# L000-Power-Schematic.net
KiCad netlist of a schematic drawn in EAGLE
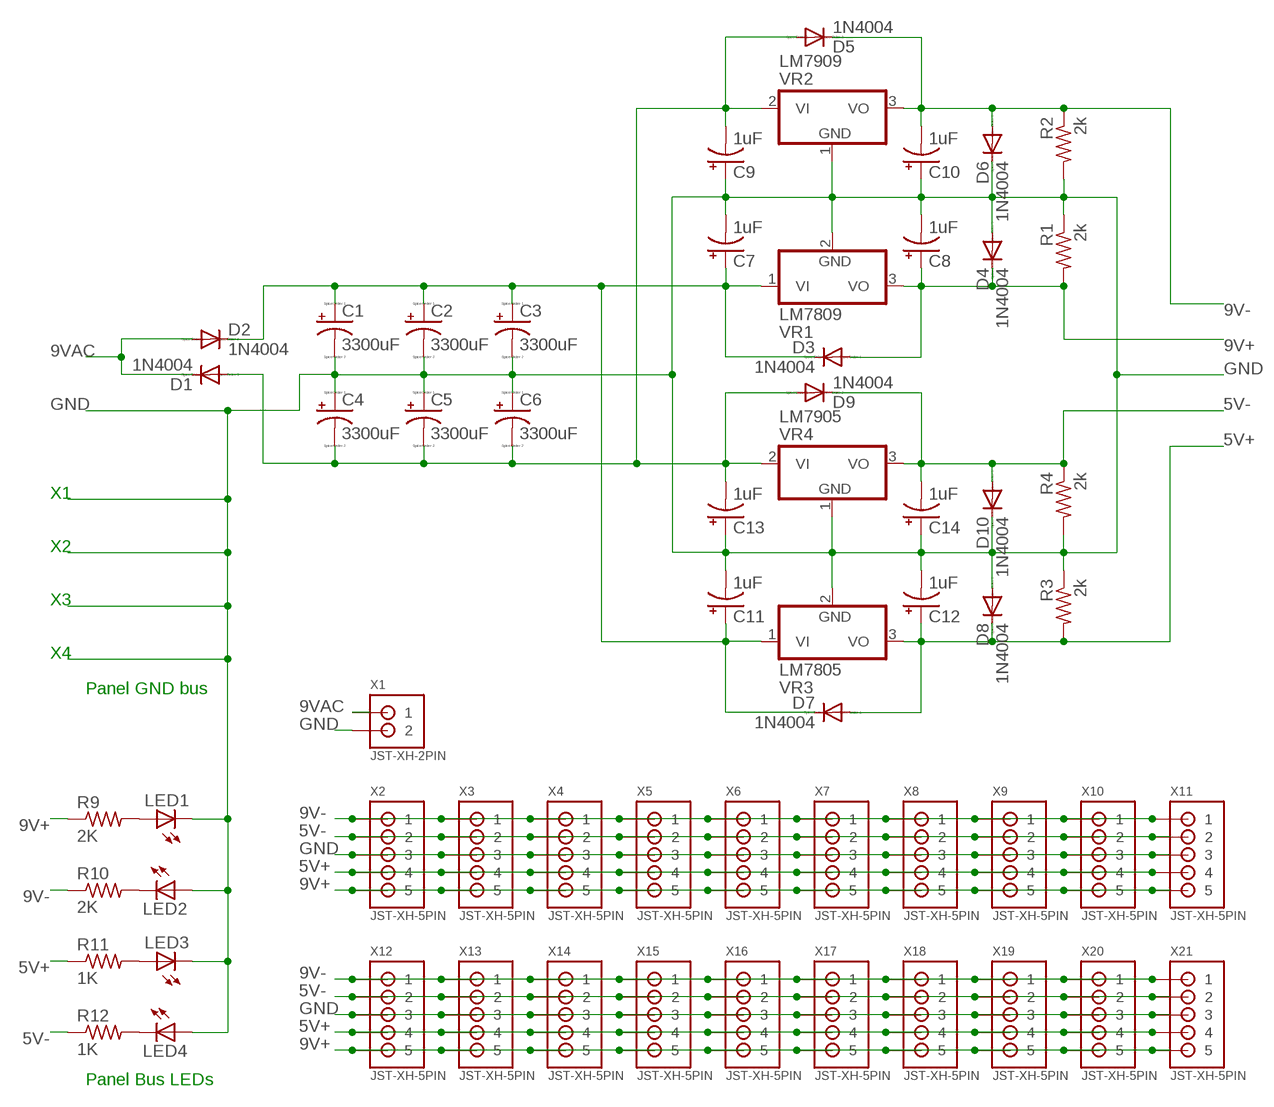
[diagram p0: schematic, sheet 1]

(export (version "E")
  (design (tool "Eeschema 10.0.6"))
  (components
    (comp (ref "C1")
      (value "3300uF")
      (footprint "eagle-import:E5-13")
      (libsource (lib "eagle-import") (part "resistor_CPOL-USE5-13"))
    )
    (comp (ref "C2")
      (value "3300uF")
      (footprint "eagle-import:E5-13")
      (libsource (lib "eagle-import") (part "resistor_CPOL-USE5-13"))
    )
    (comp (ref "C3")
      (value "3300uF")
      (footprint "eagle-import:E5-13")
      (libsource (lib "eagle-import") (part "resistor_CPOL-USE5-13"))
    )
    (comp (ref "C4")
      (value "3300uF")
      (footprint "eagle-import:E5-13")
      (libsource (lib "eagle-import") (part "resistor_CPOL-USE5-13"))
    )
    (comp (ref "C5")
      (value "3300uF")
      (footprint "eagle-import:E5-13")
      (libsource (lib "eagle-import") (part "resistor_CPOL-USE5-13"))
    )
    (comp (ref "C6")
      (value "3300uF")
      (footprint "eagle-import:E5-13")
      (libsource (lib "eagle-import") (part "resistor_CPOL-USE5-13"))
    )
    (comp (ref "C7")
      (value "1uF")
      (footprint "eagle-import:E2,5-6E")
      (libsource (lib "eagle-import") (part "CPOL-USE2,5-6E"))
    )
    (comp (ref "C8")
      (value "1uF")
      (footprint "eagle-import:E2,5-6E")
      (libsource (lib "eagle-import") (part "CPOL-USE2,5-6E"))
    )
    (comp (ref "C9")
      (value "1uF")
      (footprint "eagle-import:E2,5-6E")
      (libsource (lib "eagle-import") (part "CPOL-USE2,5-6E"))
    )
    (comp (ref "C10")
      (value "1uF")
      (footprint "eagle-import:E2,5-6E")
      (libsource (lib "eagle-import") (part "CPOL-USE2,5-6E"))
    )
    (comp (ref "C11")
      (value "1uF")
      (footprint "eagle-import:E2,5-6E")
      (libsource (lib "eagle-import") (part "CPOL-USE2,5-6E"))
    )
    (comp (ref "C12")
      (value "1uF")
      (footprint "eagle-import:E2,5-6E")
      (libsource (lib "eagle-import") (part "CPOL-USE2,5-6E"))
    )
    (comp (ref "C13")
      (value "1uF")
      (footprint "eagle-import:E2,5-6E")
      (libsource (lib "eagle-import") (part "CPOL-USE2,5-6E"))
    )
    (comp (ref "C14")
      (value "1uF")
      (footprint "eagle-import:E2,5-6E")
      (libsource (lib "eagle-import") (part "CPOL-USE2,5-6E"))
    )
    (comp (ref "D1")
      (value "1N4004")
      (footprint "eagle-import:DO41-10")
      (libsource (lib "eagle-import") (part "1N4004"))
    )
    (comp (ref "D2")
      (value "1N4004")
      (footprint "eagle-import:DO41-10")
      (libsource (lib "eagle-import") (part "1N4004"))
    )
    (comp (ref "D3")
      (value "1N4004")
      (footprint "eagle-import:DO41-10")
      (libsource (lib "eagle-import") (part "1N4004"))
    )
    (comp (ref "D4")
      (value "1N4004")
      (footprint "eagle-import:DO41-10")
      (libsource (lib "eagle-import") (part "1N4004"))
    )
    (comp (ref "D5")
      (value "1N4004")
      (footprint "eagle-import:DO41-10")
      (libsource (lib "eagle-import") (part "1N4004"))
    )
    (comp (ref "D6")
      (value "1N4004")
      (footprint "eagle-import:DO41-10")
      (libsource (lib "eagle-import") (part "1N4004"))
    )
    (comp (ref "D7")
      (value "1N4004")
      (footprint "eagle-import:DO41-10")
      (libsource (lib "eagle-import") (part "1N4004"))
    )
    (comp (ref "D8")
      (value "1N4004")
      (footprint "eagle-import:DO41-10")
      (libsource (lib "eagle-import") (part "1N4004"))
    )
    (comp (ref "D9")
      (value "1N4004")
      (footprint "eagle-import:DO41-10")
      (libsource (lib "eagle-import") (part "1N4004"))
    )
    (comp (ref "D10")
      (value "1N4004")
      (footprint "eagle-import:DO41-10")
      (libsource (lib "eagle-import") (part "1N4004"))
    )
    (comp (ref "LED1")
      (value "LED5MM")
      (footprint "eagle-import:LED5MM")
      (libsource (lib "eagle-import") (part "LED5MM"))
    )
    (comp (ref "LED2")
      (value "LED5MM")
      (footprint "eagle-import:LED5MM")
      (libsource (lib "eagle-import") (part "LED5MM"))
    )
    (comp (ref "LED3")
      (value "LED5MM")
      (footprint "eagle-import:LED5MM")
      (libsource (lib "eagle-import") (part "LED5MM"))
    )
    (comp (ref "LED4")
      (value "LED5MM")
      (footprint "eagle-import:LED5MM")
      (libsource (lib "eagle-import") (part "LED5MM"))
    )
    (comp (ref "R1")
      (value "2k")
      (footprint "eagle-import:0309_10")
      (libsource (lib "eagle-import") (part "R-US_0309/10"))
    )
    (comp (ref "R2")
      (value "2k")
      (footprint "eagle-import:0309_10")
      (libsource (lib "eagle-import") (part "R-US_0309/10"))
    )
    (comp (ref "R3")
      (value "2k")
      (footprint "eagle-import:0309_10")
      (libsource (lib "eagle-import") (part "R-US_0309/10"))
    )
    (comp (ref "R4")
      (value "2k")
      (footprint "eagle-import:0309_10")
      (libsource (lib "eagle-import") (part "R-US_0309/10"))
    )
    (comp (ref "R9")
      (value "2K")
      (footprint "eagle-import:0309_10")
      (libsource (lib "eagle-import") (part "R-US_0309/10"))
    )
    (comp (ref "R10")
      (value "2K")
      (footprint "eagle-import:0309_10")
      (libsource (lib "eagle-import") (part "R-US_0309/10"))
    )
    (comp (ref "R11")
      (value "1K")
      (footprint "eagle-import:0309_10")
      (libsource (lib "eagle-import") (part "R-US_0309/10"))
    )
    (comp (ref "R12")
      (value "1K")
      (footprint "eagle-import:0309_10")
      (libsource (lib "eagle-import") (part "R-US_0309/10"))
    )
    (comp (ref "VR1")
      (value "LM7809")
      (footprint "eagle-import:TO220H")
      (libsource (lib "eagle-import") (part "78T08"))
    )
    (comp (ref "VR2")
      (value "LM7909")
      (footprint "eagle-import:TO220H")
      (libsource (lib "eagle-import") (part "79T08"))
    )
    (comp (ref "VR3")
      (value "LM7805")
      (footprint "eagle-import:TO220H")
      (libsource (lib "eagle-import") (part "78T05"))
    )
    (comp (ref "VR4")
      (value "LM7905")
      (footprint "eagle-import:TO220H")
      (libsource (lib "eagle-import") (part "79T05"))
    )
    (comp (ref "X1")
      (value "JST-XH-2PIN")
      (footprint "eagle-import:JST_B2B-PH_HEADER")
      (libsource (lib "eagle-import") (part "JST-PH_2-PIN_HEADER"))
    )
    (comp (ref "X2")
      (value "JST-XH-5PIN")
      (footprint "eagle-import:JST_B5B-PH_HEADER")
      (libsource (lib "eagle-import") (part "JST-PH_5-PIN_HEADER"))
    )
    (comp (ref "X3")
      (value "JST-XH-5PIN")
      (footprint "eagle-import:JST_B5B-PH_HEADER")
      (libsource (lib "eagle-import") (part "JST-PH_5-PIN_HEADER"))
    )
    (comp (ref "X4")
      (value "JST-XH-5PIN")
      (footprint "eagle-import:JST_B5B-PH_HEADER")
      (libsource (lib "eagle-import") (part "JST-PH_5-PIN_HEADER"))
    )
    (comp (ref "X5")
      (value "JST-XH-5PIN")
      (footprint "eagle-import:JST_B5B-PH_HEADER")
      (libsource (lib "eagle-import") (part "JST-PH_5-PIN_HEADER"))
    )
    (comp (ref "X6")
      (value "JST-XH-5PIN")
      (footprint "eagle-import:JST_B5B-PH_HEADER")
      (libsource (lib "eagle-import") (part "JST-PH_5-PIN_HEADER"))
    )
    (comp (ref "X7")
      (value "JST-XH-5PIN")
      (footprint "eagle-import:JST_B5B-PH_HEADER")
      (libsource (lib "eagle-import") (part "JST-PH_5-PIN_HEADER"))
    )
    (comp (ref "X8")
      (value "JST-XH-5PIN")
      (footprint "eagle-import:JST_B5B-PH_HEADER")
      (libsource (lib "eagle-import") (part "JST-PH_5-PIN_HEADER"))
    )
    (comp (ref "X9")
      (value "JST-XH-5PIN")
      (footprint "eagle-import:JST_B5B-PH_HEADER")
      (libsource (lib "eagle-import") (part "JST-PH_5-PIN_HEADER"))
    )
    (comp (ref "X10")
      (value "JST-XH-5PIN")
      (footprint "eagle-import:JST_B5B-PH_HEADER")
      (libsource (lib "eagle-import") (part "JST-PH_5-PIN_HEADER"))
    )
    (comp (ref "X11")
      (value "JST-XH-5PIN")
      (footprint "eagle-import:JST_B5B-PH_HEADER")
      (libsource (lib "eagle-import") (part "JST-PH_5-PIN_HEADER"))
    )
    (comp (ref "X12")
      (value "JST-XH-5PIN")
      (footprint "eagle-import:JST_B5B-PH_HEADER")
      (libsource (lib "eagle-import") (part "JST-PH_5-PIN_HEADER"))
    )
    (comp (ref "X13")
      (value "JST-XH-5PIN")
      (footprint "eagle-import:JST_B5B-PH_HEADER")
      (libsource (lib "eagle-import") (part "JST-PH_5-PIN_HEADER"))
    )
    (comp (ref "X14")
      (value "JST-XH-5PIN")
      (footprint "eagle-import:JST_B5B-PH_HEADER")
      (libsource (lib "eagle-import") (part "JST-PH_5-PIN_HEADER"))
    )
    (comp (ref "X15")
      (value "JST-XH-5PIN")
      (footprint "eagle-import:JST_B5B-PH_HEADER")
      (libsource (lib "eagle-import") (part "JST-PH_5-PIN_HEADER"))
    )
    (comp (ref "X16")
      (value "JST-XH-5PIN")
      (footprint "eagle-import:JST_B5B-PH_HEADER")
      (libsource (lib "eagle-import") (part "JST-PH_5-PIN_HEADER"))
    )
    (comp (ref "X17")
      (value "JST-XH-5PIN")
      (footprint "eagle-import:JST_B5B-PH_HEADER")
      (libsource (lib "eagle-import") (part "JST-PH_5-PIN_HEADER"))
    )
    (comp (ref "X18")
      (value "JST-XH-5PIN")
      (footprint "eagle-import:JST_B5B-PH_HEADER")
      (libsource (lib "eagle-import") (part "JST-PH_5-PIN_HEADER"))
    )
    (comp (ref "X19")
      (value "JST-XH-5PIN")
      (footprint "eagle-import:JST_B5B-PH_HEADER")
      (libsource (lib "eagle-import") (part "JST-PH_5-PIN_HEADER"))
    )
    (comp (ref "X20")
      (value "JST-XH-5PIN")
      (footprint "eagle-import:JST_B5B-PH_HEADER")
      (libsource (lib "eagle-import") (part "JST-PH_5-PIN_HEADER"))
    )
    (comp (ref "X21")
      (value "JST-XH-5PIN")
      (footprint "eagle-import:JST_B5B-PH_HEADER")
      (libsource (lib "eagle-import") (part "JST-PH_5-PIN_HEADER"))
    )
  )
  (nets
    (net (code "1") (name "/5V+") (class "Default")
      (node (ref "C12") (pin "+") (pinfunction "+_+") (pintype "passive"))
      (node (ref "D7") (pin "A") (pinfunction "A_A") (pintype "passive"))
      (node (ref "D8") (pin "C") (pinfunction "C_C") (pintype "passive"))
      (node (ref "R11") (pin "1") (pinfunction "1_1") (pintype "passive"))
      (node (ref "R3") (pin "2") (pinfunction "2_2") (pintype "passive"))
      (node (ref "VR3") (pin "3") (pinfunction "VO_3") (pintype "passive"))
      (node (ref "X10") (pin "P4") (pinfunction "4_P4") (pintype "bidirectional"))
      (node (ref "X11") (pin "P4") (pinfunction "4_P4") (pintype "bidirectional"))
      (node (ref "X12") (pin "P4") (pinfunction "4_P4") (pintype "bidirectional"))
      (node (ref "X13") (pin "P4") (pinfunction "4_P4") (pintype "bidirectional"))
      (node (ref "X14") (pin "P4") (pinfunction "4_P4") (pintype "bidirectional"))
      (node (ref "X15") (pin "P4") (pinfunction "4_P4") (pintype "bidirectional"))
      (node (ref "X16") (pin "P4") (pinfunction "4_P4") (pintype "bidirectional"))
      (node (ref "X17") (pin "P4") (pinfunction "4_P4") (pintype "bidirectional"))
      (node (ref "X18") (pin "P4") (pinfunction "4_P4") (pintype "bidirectional"))
      (node (ref "X19") (pin "P4") (pinfunction "4_P4") (pintype "bidirectional"))
      (node (ref "X2") (pin "P4") (pinfunction "4_P4") (pintype "bidirectional"))
      (node (ref "X20") (pin "P4") (pinfunction "4_P4") (pintype "bidirectional"))
      (node (ref "X21") (pin "P4") (pinfunction "4_P4") (pintype "bidirectional"))
      (node (ref "X3") (pin "P4") (pinfunction "4_P4") (pintype "bidirectional"))
      (node (ref "X4") (pin "P4") (pinfunction "4_P4") (pintype "bidirectional"))
      (node (ref "X5") (pin "P4") (pinfunction "4_P4") (pintype "bidirectional"))
      (node (ref "X6") (pin "P4") (pinfunction "4_P4") (pintype "bidirectional"))
      (node (ref "X7") (pin "P4") (pinfunction "4_P4") (pintype "bidirectional"))
      (node (ref "X8") (pin "P4") (pinfunction "4_P4") (pintype "bidirectional"))
      (node (ref "X9") (pin "P4") (pinfunction "4_P4") (pintype "bidirectional"))
    )
    (net (code "2") (name "/5V-") (class "Default")
      (node (ref "C14") (pin "-") (pinfunction "-_-") (pintype "passive"))
      (node (ref "D10") (pin "A") (pinfunction "A_A") (pintype "passive"))
      (node (ref "D9") (pin "C") (pinfunction "C_C") (pintype "passive"))
      (node (ref "R12") (pin "1") (pinfunction "1_1") (pintype "passive"))
      (node (ref "R4") (pin "1") (pinfunction "1_1") (pintype "passive"))
      (node (ref "VR4") (pin "3") (pinfunction "VO_3") (pintype "passive"))
      (node (ref "X10") (pin "P2") (pinfunction "2_P2") (pintype "bidirectional"))
      (node (ref "X11") (pin "P2") (pinfunction "2_P2") (pintype "bidirectional"))
      (node (ref "X12") (pin "P2") (pinfunction "2_P2") (pintype "bidirectional"))
      (node (ref "X13") (pin "P2") (pinfunction "2_P2") (pintype "bidirectional"))
      (node (ref "X14") (pin "P2") (pinfunction "2_P2") (pintype "bidirectional"))
      (node (ref "X15") (pin "P2") (pinfunction "2_P2") (pintype "bidirectional"))
      (node (ref "X16") (pin "P2") (pinfunction "2_P2") (pintype "bidirectional"))
      (node (ref "X17") (pin "P2") (pinfunction "2_P2") (pintype "bidirectional"))
      (node (ref "X18") (pin "P2") (pinfunction "2_P2") (pintype "bidirectional"))
      (node (ref "X19") (pin "P2") (pinfunction "2_P2") (pintype "bidirectional"))
      (node (ref "X2") (pin "P2") (pinfunction "2_P2") (pintype "bidirectional"))
      (node (ref "X20") (pin "P2") (pinfunction "2_P2") (pintype "bidirectional"))
      (node (ref "X21") (pin "P2") (pinfunction "2_P2") (pintype "bidirectional"))
      (node (ref "X3") (pin "P2") (pinfunction "2_P2") (pintype "bidirectional"))
      (node (ref "X4") (pin "P2") (pinfunction "2_P2") (pintype "bidirectional"))
      (node (ref "X5") (pin "P2") (pinfunction "2_P2") (pintype "bidirectional"))
      (node (ref "X6") (pin "P2") (pinfunction "2_P2") (pintype "bidirectional"))
      (node (ref "X7") (pin "P2") (pinfunction "2_P2") (pintype "bidirectional"))
      (node (ref "X8") (pin "P2") (pinfunction "2_P2") (pintype "bidirectional"))
      (node (ref "X9") (pin "P2") (pinfunction "2_P2") (pintype "bidirectional"))
    )
    (net (code "3") (name "/9V+") (class "Default")
      (node (ref "C8") (pin "+") (pinfunction "+_+") (pintype "passive"))
      (node (ref "D3") (pin "A") (pinfunction "A_A") (pintype "passive"))
      (node (ref "D4") (pin "C") (pinfunction "C_C") (pintype "passive"))
      (node (ref "R1") (pin "2") (pinfunction "2_2") (pintype "passive"))
      (node (ref "R9") (pin "1") (pinfunction "1_1") (pintype "passive"))
      (node (ref "VR1") (pin "3") (pinfunction "VO_3") (pintype "passive"))
      (node (ref "X10") (pin "P5") (pinfunction "5_P5") (pintype "bidirectional"))
      (node (ref "X11") (pin "P5") (pinfunction "5_P5") (pintype "bidirectional"))
      (node (ref "X12") (pin "P5") (pinfunction "5_P5") (pintype "bidirectional"))
      (node (ref "X13") (pin "P5") (pinfunction "5_P5") (pintype "bidirectional"))
      (node (ref "X14") (pin "P5") (pinfunction "5_P5") (pintype "bidirectional"))
      (node (ref "X15") (pin "P5") (pinfunction "5_P5") (pintype "bidirectional"))
      (node (ref "X16") (pin "P5") (pinfunction "5_P5") (pintype "bidirectional"))
      (node (ref "X17") (pin "P5") (pinfunction "5_P5") (pintype "bidirectional"))
      (node (ref "X18") (pin "P5") (pinfunction "5_P5") (pintype "bidirectional"))
      (node (ref "X19") (pin "P5") (pinfunction "5_P5") (pintype "bidirectional"))
      (node (ref "X2") (pin "P5") (pinfunction "5_P5") (pintype "bidirectional"))
      (node (ref "X20") (pin "P5") (pinfunction "5_P5") (pintype "bidirectional"))
      (node (ref "X21") (pin "P5") (pinfunction "5_P5") (pintype "bidirectional"))
      (node (ref "X3") (pin "P5") (pinfunction "5_P5") (pintype "bidirectional"))
      (node (ref "X4") (pin "P5") (pinfunction "5_P5") (pintype "bidirectional"))
      (node (ref "X5") (pin "P5") (pinfunction "5_P5") (pintype "bidirectional"))
      (node (ref "X6") (pin "P5") (pinfunction "5_P5") (pintype "bidirectional"))
      (node (ref "X7") (pin "P5") (pinfunction "5_P5") (pintype "bidirectional"))
      (node (ref "X8") (pin "P5") (pinfunction "5_P5") (pintype "bidirectional"))
      (node (ref "X9") (pin "P5") (pinfunction "5_P5") (pintype "bidirectional"))
    )
    (net (code "4") (name "/9V-") (class "Default")
      (node (ref "C10") (pin "-") (pinfunction "-_-") (pintype "passive"))
      (node (ref "D5") (pin "C") (pinfunction "C_C") (pintype "passive"))
      (node (ref "D6") (pin "A") (pinfunction "A_A") (pintype "passive"))
      (node (ref "R10") (pin "1") (pinfunction "1_1") (pintype "passive"))
      (node (ref "R2") (pin "1") (pinfunction "1_1") (pintype "passive"))
      (node (ref "VR2") (pin "3") (pinfunction "VO_3") (pintype "passive"))
      (node (ref "X10") (pin "P1") (pinfunction "1_P1") (pintype "bidirectional"))
      (node (ref "X11") (pin "P1") (pinfunction "1_P1") (pintype "bidirectional"))
      (node (ref "X12") (pin "P1") (pinfunction "1_P1") (pintype "bidirectional"))
      (node (ref "X13") (pin "P1") (pinfunction "1_P1") (pintype "bidirectional"))
      (node (ref "X14") (pin "P1") (pinfunction "1_P1") (pintype "bidirectional"))
      (node (ref "X15") (pin "P1") (pinfunction "1_P1") (pintype "bidirectional"))
      (node (ref "X16") (pin "P1") (pinfunction "1_P1") (pintype "bidirectional"))
      (node (ref "X17") (pin "P1") (pinfunction "1_P1") (pintype "bidirectional"))
      (node (ref "X18") (pin "P1") (pinfunction "1_P1") (pintype "bidirectional"))
      (node (ref "X19") (pin "P1") (pinfunction "1_P1") (pintype "bidirectional"))
      (node (ref "X2") (pin "P1") (pinfunction "1_P1") (pintype "bidirectional"))
      (node (ref "X20") (pin "P1") (pinfunction "1_P1") (pintype "bidirectional"))
      (node (ref "X21") (pin "P1") (pinfunction "1_P1") (pintype "bidirectional"))
      (node (ref "X3") (pin "P1") (pinfunction "1_P1") (pintype "bidirectional"))
      (node (ref "X4") (pin "P1") (pinfunction "1_P1") (pintype "bidirectional"))
      (node (ref "X5") (pin "P1") (pinfunction "1_P1") (pintype "bidirectional"))
      (node (ref "X6") (pin "P1") (pinfunction "1_P1") (pintype "bidirectional"))
      (node (ref "X7") (pin "P1") (pinfunction "1_P1") (pintype "bidirectional"))
      (node (ref "X8") (pin "P1") (pinfunction "1_P1") (pintype "bidirectional"))
      (node (ref "X9") (pin "P1") (pinfunction "1_P1") (pintype "bidirectional"))
    )
    (net (code "5") (name "/9VAC") (class "Default")
      (node (ref "D1") (pin "C") (pinfunction "C_C") (pintype "passive"))
      (node (ref "D2") (pin "A") (pinfunction "A_A") (pintype "passive"))
      (node (ref "X1") (pin "P1") (pinfunction "1_P1") (pintype "bidirectional"))
    )
    (net (code "6") (name "/GND") (class "Default")
      (node (ref "C1") (pin "-") (pinfunction "-_-") (pintype "passive"))
      (node (ref "C10") (pin "+") (pinfunction "+_+") (pintype "passive"))
      (node (ref "C11") (pin "-") (pinfunction "-_-") (pintype "passive"))
      (node (ref "C12") (pin "-") (pinfunction "-_-") (pintype "passive"))
      (node (ref "C13") (pin "+") (pinfunction "+_+") (pintype "passive"))
      (node (ref "C14") (pin "+") (pinfunction "+_+") (pintype "passive"))
      (node (ref "C2") (pin "-") (pinfunction "-_-") (pintype "passive"))
      (node (ref "C3") (pin "-") (pinfunction "-_-") (pintype "passive"))
      (node (ref "C4") (pin "+") (pinfunction "+_+") (pintype "passive"))
      (node (ref "C5") (pin "+") (pinfunction "+_+") (pintype "passive"))
      (node (ref "C6") (pin "+") (pinfunction "+_+") (pintype "passive"))
      (node (ref "C7") (pin "-") (pinfunction "-_-") (pintype "passive"))
      (node (ref "C8") (pin "-") (pinfunction "-_-") (pintype "passive"))
      (node (ref "C9") (pin "+") (pinfunction "+_+") (pintype "passive"))
      (node (ref "D10") (pin "C") (pinfunction "C_C") (pintype "passive"))
      (node (ref "D4") (pin "A") (pinfunction "A_A") (pintype "passive"))
      (node (ref "D6") (pin "C") (pinfunction "C_C") (pintype "passive"))
      (node (ref "D8") (pin "A") (pinfunction "A_A") (pintype "passive"))
      (node (ref "LED1") (pin "K") (pinfunction "C_K") (pintype "passive"))
      (node (ref "LED2") (pin "A") (pinfunction "A_A") (pintype "passive"))
      (node (ref "LED3") (pin "K") (pinfunction "C_K") (pintype "passive"))
      (node (ref "LED4") (pin "A") (pinfunction "A_A") (pintype "passive"))
      (node (ref "R1") (pin "1") (pinfunction "1_1") (pintype "passive"))
      (node (ref "R2") (pin "2") (pinfunction "2_2") (pintype "passive"))
      (node (ref "R3") (pin "1") (pinfunction "1_1") (pintype "passive"))
      (node (ref "R4") (pin "2") (pinfunction "2_2") (pintype "passive"))
      (node (ref "VR1") (pin "2") (pinfunction "GND_2") (pintype "passive"))
      (node (ref "VR2") (pin "1") (pinfunction "GND_1") (pintype "passive"))
      (node (ref "VR3") (pin "2") (pinfunction "GND_2") (pintype "passive"))
      (node (ref "VR4") (pin "1") (pinfunction "GND_1") (pintype "passive"))
      (node (ref "X1") (pin "P2") (pinfunction "2_P2") (pintype "bidirectional"))
      (node (ref "X10") (pin "P3") (pinfunction "3_P3") (pintype "bidirectional"))
      (node (ref "X11") (pin "P3") (pinfunction "3_P3") (pintype "bidirectional"))
      (node (ref "X12") (pin "P3") (pinfunction "3_P3") (pintype "bidirectional"))
      (node (ref "X13") (pin "P3") (pinfunction "3_P3") (pintype "bidirectional"))
      (node (ref "X14") (pin "P3") (pinfunction "3_P3") (pintype "bidirectional"))
      (node (ref "X15") (pin "P3") (pinfunction "3_P3") (pintype "bidirectional"))
      (node (ref "X16") (pin "P3") (pinfunction "3_P3") (pintype "bidirectional"))
      (node (ref "X17") (pin "P3") (pinfunction "3_P3") (pintype "bidirectional"))
      (node (ref "X18") (pin "P3") (pinfunction "3_P3") (pintype "bidirectional"))
      (node (ref "X19") (pin "P3") (pinfunction "3_P3") (pintype "bidirectional"))
      (node (ref "X2") (pin "P3") (pinfunction "3_P3") (pintype "bidirectional"))
      (node (ref "X20") (pin "P3") (pinfunction "3_P3") (pintype "bidirectional"))
      (node (ref "X21") (pin "P3") (pinfunction "3_P3") (pintype "bidirectional"))
      (node (ref "X3") (pin "P3") (pinfunction "3_P3") (pintype "bidirectional"))
      (node (ref "X4") (pin "P3") (pinfunction "3_P3") (pintype "bidirectional"))
      (node (ref "X5") (pin "P3") (pinfunction "3_P3") (pintype "bidirectional"))
      (node (ref "X6") (pin "P3") (pinfunction "3_P3") (pintype "bidirectional"))
      (node (ref "X7") (pin "P3") (pinfunction "3_P3") (pintype "bidirectional"))
      (node (ref "X8") (pin "P3") (pinfunction "3_P3") (pintype "bidirectional"))
      (node (ref "X9") (pin "P3") (pinfunction "3_P3") (pintype "bidirectional"))
    )
    (net (code "7") (name "Net-(LED1-PadA)") (class "Default")
      (node (ref "LED1") (pin "A") (pinfunction "A_A") (pintype "passive"))
      (node (ref "R9") (pin "2") (pinfunction "2_2") (pintype "passive"))
    )
    (net (code "8") (name "Net-(LED2-C)") (class "Default")
      (node (ref "LED2") (pin "K") (pinfunction "C_K") (pintype "passive"))
      (node (ref "R10") (pin "2") (pinfunction "2_2") (pintype "passive"))
    )
    (net (code "9") (name "Net-(LED3-PadA)") (class "Default")
      (node (ref "LED3") (pin "A") (pinfunction "A_A") (pintype "passive"))
      (node (ref "R11") (pin "2") (pinfunction "2_2") (pintype "passive"))
    )
    (net (code "10") (name "Net-(LED4-C)") (class "Default")
      (node (ref "LED4") (pin "K") (pinfunction "C_K") (pintype "passive"))
      (node (ref "R12") (pin "2") (pinfunction "2_2") (pintype "passive"))
    )
    (net (code "11") (name "Net-(VR1-VI)") (class "Default")
      (node (ref "C1") (pin "+") (pinfunction "+_+") (pintype "passive"))
      (node (ref "C11") (pin "+") (pinfunction "+_+") (pintype "passive"))
      (node (ref "C2") (pin "+") (pinfunction "+_+") (pintype "passive"))
      (node (ref "C3") (pin "+") (pinfunction "+_+") (pintype "passive"))
      (node (ref "C7") (pin "+") (pinfunction "+_+") (pintype "passive"))
      (node (ref "D2") (pin "C") (pinfunction "C_C") (pintype "passive"))
      (node (ref "D3") (pin "C") (pinfunction "C_C") (pintype "passive"))
      (node (ref "D7") (pin "C") (pinfunction "C_C") (pintype "passive"))
      (node (ref "VR1") (pin "1") (pinfunction "VI_1") (pintype "input"))
      (node (ref "VR3") (pin "1") (pinfunction "VI_1") (pintype "input"))
    )
    (net (code "12") (name "Net-(VR2-VI)") (class "Default")
      (node (ref "C13") (pin "-") (pinfunction "-_-") (pintype "passive"))
      (node (ref "C4") (pin "-") (pinfunction "-_-") (pintype "passive"))
      (node (ref "C5") (pin "-") (pinfunction "-_-") (pintype "passive"))
      (node (ref "C6") (pin "-") (pinfunction "-_-") (pintype "passive"))
      (node (ref "C9") (pin "-") (pinfunction "-_-") (pintype "passive"))
      (node (ref "D1") (pin "A") (pinfunction "A_A") (pintype "passive"))
      (node (ref "D5") (pin "A") (pinfunction "A_A") (pintype "passive"))
      (node (ref "D9") (pin "A") (pinfunction "A_A") (pintype "passive"))
      (node (ref "VR2") (pin "2") (pinfunction "VI_2") (pintype "input"))
      (node (ref "VR4") (pin "2") (pinfunction "VI_2") (pintype "input"))
    )
  )
)
